# M_D_ext_power-solar-moved-usb.net
KiCad netlist of a schematic drawn in EAGLE
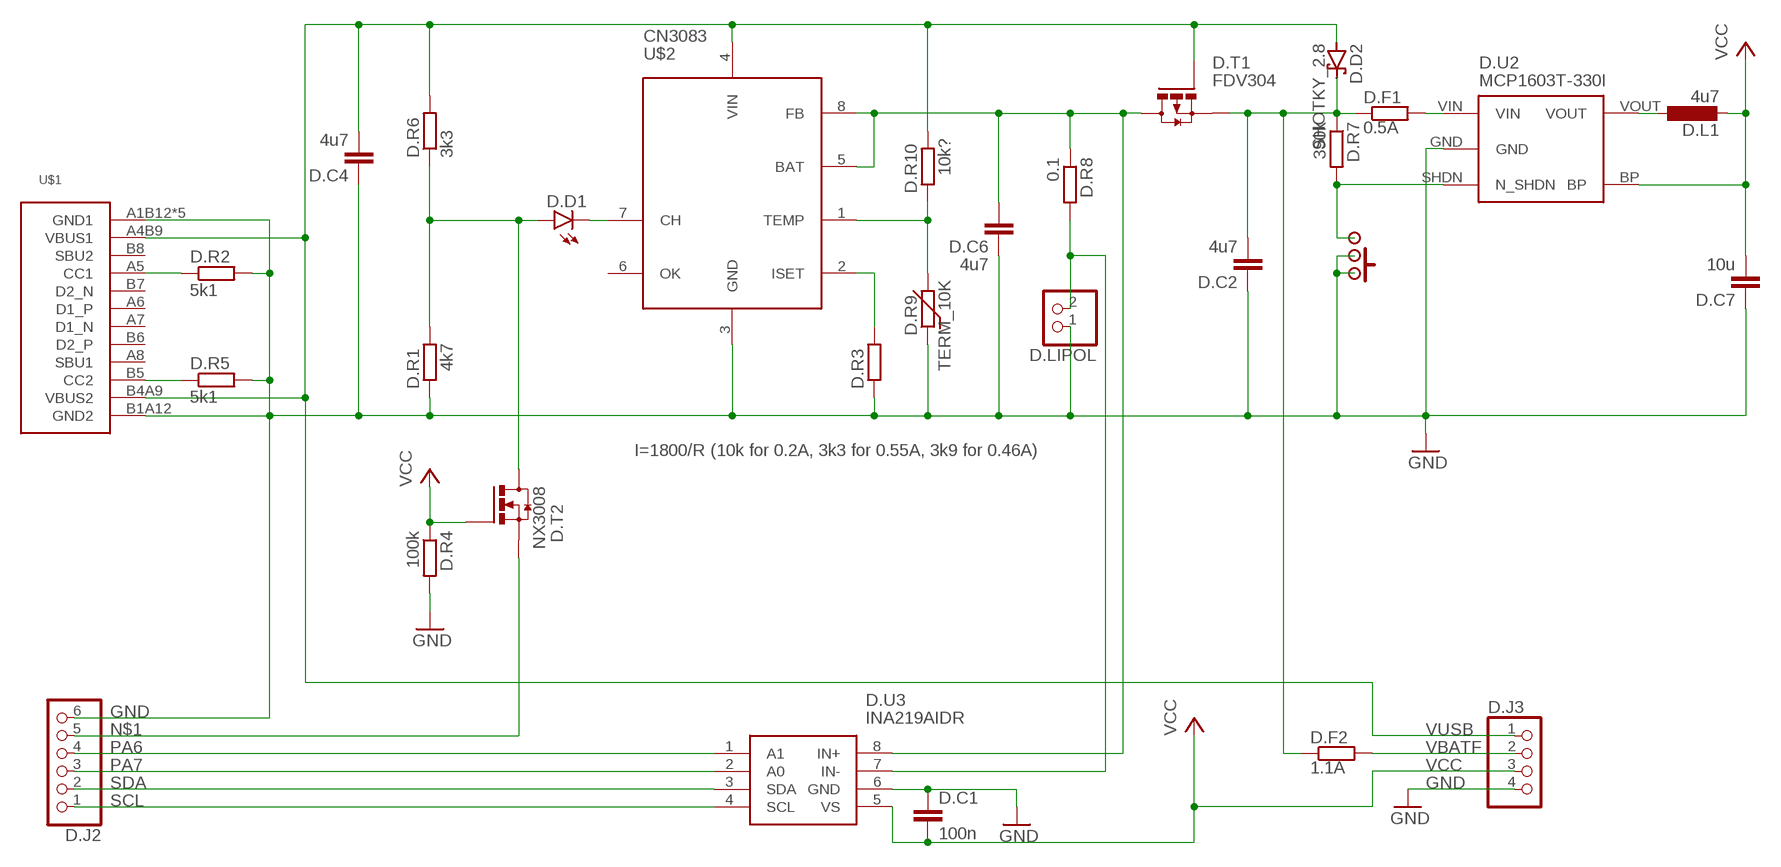
[diagram p0: schematic, sheet 1]

(export (version "E")
  (design (tool "Eeschema 10.0.6"))
  (components
    (comp (ref "D.C1")
      (value "100n")
      (footprint "eagle-import:C0603")
      (libsource (lib "eagle-import") (part "C-EUC0603"))
    )
    (comp (ref "D.C2")
      (value "4u7")
      (footprint "eagle-import:C0603")
      (libsource (lib "eagle-import") (part "C-EUC0603"))
    )
    (comp (ref "D.C4")
      (value "4u7")
      (footprint "eagle-import:C0603")
      (libsource (lib "eagle-import") (part "C-EUC0603"))
    )
    (comp (ref "D.C6")
      (value "4u7")
      (footprint "eagle-import:C0603")
      (libsource (lib "eagle-import") (part "C-EUC0603"))
    )
    (comp (ref "D.C7")
      (value "10u")
      (footprint "eagle-import:C0805")
      (libsource (lib "eagle-import") (part "C-EUC0805"))
    )
    (comp (ref "D.D1")
      (value "LEDCHIP-LED0603")
      (footprint "eagle-import:CHIP-LED0603")
      (libsource (lib "eagle-import") (part "LEDCHIP-LED0603"))
    )
    (comp (ref "D.D2")
      (value "SHOTKY_2.8")
      (footprint "eagle-import:SHOTKY_2.8")
      (libsource (lib "eagle-import") (part "SHOTKY_2.8"))
    )
    (comp (ref "D.F1")
      (value "0.5A")
      (footprint "eagle-import:R0805")
      (libsource (lib "eagle-import") (part "R-EU_R0805"))
    )
    (comp (ref "D.F2")
      (value "1.1A")
      (footprint "eagle-import:R0805")
      (libsource (lib "eagle-import") (part "R-EU_R0805"))
    )
    (comp (ref "D.J2")
      (value "PINHD-1X6")
      (footprint "eagle-import:1X06")
      (libsource (lib "eagle-import") (part "PINHD-1X6"))
    )
    (comp (ref "D.J3")
      (value "PINHD-1X4")
      (footprint "eagle-import:1X04")
      (libsource (lib "eagle-import") (part "PINHD-1X4"))
    )
    (comp (ref "D.L1")
      (value "4u7")
      (footprint "eagle-import:L3230M")
      (libsource (lib "eagle-import") (part "L-EUL3230M"))
    )
    (comp (ref "D.LIPOL")
      (value "PINHD-1X2")
      (footprint "eagle-import:1X02")
      (libsource (lib "eagle-import") (part "PINHD-1X2"))
    )
    (comp (ref "D.ON/OFF/RESET")
      (value "SWITCH")
      (footprint "eagle-import:SWITCH")
      (libsource (lib "eagle-import") (part "SWITCH"))
    )
    (comp (ref "D.R1")
      (value "4k7")
      (footprint "eagle-import:R0603")
      (libsource (lib "eagle-import") (part "R-EU_R0603"))
    )
    (comp (ref "D.R2")
      (value "5k1")
      (footprint "eagle-import:R0603")
      (libsource (lib "eagle-import") (part "R-EU_R0603"))
    )
    (comp (ref "D.R3")
      (value "I=1800/R (10k for 0.2A, 3k3 for 0.55A, 3k9 for 0.46A)")
      (footprint "eagle-import:R0603")
      (libsource (lib "eagle-import") (part "R-EU_R0603"))
    )
    (comp (ref "D.R4")
      (value "100k")
      (footprint "eagle-import:R0603")
      (libsource (lib "eagle-import") (part "R-EU_R0603"))
    )
    (comp (ref "D.R5")
      (value "5k1")
      (footprint "eagle-import:R0603")
      (libsource (lib "eagle-import") (part "R-EU_R0603"))
    )
    (comp (ref "D.R6")
      (value "3k3")
      (footprint "eagle-import:R0603")
      (libsource (lib "eagle-import") (part "R-EU_R0603"))
    )
    (comp (ref "D.R7")
      (value "390k")
      (footprint "eagle-import:R0603")
      (libsource (lib "eagle-import") (part "R-EU_R0603"))
    )
    (comp (ref "D.R8")
      (value "0.1")
      (footprint "eagle-import:R0805")
      (libsource (lib "eagle-import") (part "R-EU_R0805"))
    )
    (comp (ref "D.R9")
      (value "TERM_10K")
      (footprint "eagle-import:THERM")
      (libsource (lib "eagle-import") (part "THERM"))
    )
    (comp (ref "D.R10")
      (value "10k?")
      (footprint "eagle-import:R0603")
      (libsource (lib "eagle-import") (part "R-EU_R0603"))
    )
    (comp (ref "D.T1")
      (value "FDV304")
      (footprint "eagle-import:SO23")
      (libsource (lib "eagle-import") (part "P-MOSFET"))
    )
    (comp (ref "D.T2")
      (value "NX3008")
      (footprint "eagle-import:SO23")
      (libsource (lib "eagle-import") (part "N-MOSFET"))
    )
    (comp (ref "D.U2")
      (value "MCP1603T-330I")
      (footprint "eagle-import:SOT32-5")
      (libsource (lib "eagle-import") (part "STABILISER_APE8865"))
    )
    (comp (ref "D.U3")
      (value "INA219AIDR")
      (footprint "eagle-import:SOIC127P600X175-8N")
      (fields (field (name "MOUSER_PART_NUMBER") "595-INA219AIDR"))
      (libsource (lib "eagle-import") (part "INA219AIDR"))
    )
    (comp (ref "U$1")
      (value "USB-C")
      (footprint "eagle-import:USB-C")
      (libsource (lib "eagle-import") (part "USB-C"))
    )
    (comp (ref "U$2")
      (value "CN3083")
      (footprint "eagle-import:SOP8")
      (libsource (lib "eagle-import") (part "CN3083"))
    )
  )
  (nets
    (net (code "1") (name "/N$1") (class "Default")
      (node (ref "D.J2") (pin "5") (pinfunction "5_5") (pintype "passive"))
      (node (ref "D.T2") (pin "S") (pinfunction "S_S") (pintype "passive"))
    )
    (net (code "2") (name "/PA6") (class "Default")
      (node (ref "D.J2") (pin "4") (pinfunction "4_4") (pintype "passive"))
      (node (ref "D.U3") (pin "1") (pinfunction "A1_1") (pintype "bidirectional"))
    )
    (net (code "3") (name "/PA7") (class "Default")
      (node (ref "D.J2") (pin "3") (pinfunction "3_3") (pintype "passive"))
      (node (ref "D.U3") (pin "2") (pinfunction "A0_2") (pintype "bidirectional"))
    )
    (net (code "4") (name "/SCL") (class "Default")
      (node (ref "D.J2") (pin "1") (pinfunction "1_1") (pintype "passive"))
      (node (ref "D.U3") (pin "4") (pinfunction "SCL_4") (pintype "bidirectional"))
    )
    (net (code "5") (name "/SDA") (class "Default")
      (node (ref "D.J2") (pin "2") (pinfunction "2_2") (pintype "passive"))
      (node (ref "D.U3") (pin "3") (pinfunction "SDA_3") (pintype "bidirectional"))
    )
    (net (code "6") (name "/VBATF") (class "Default")
      (node (ref "D.F2") (pin "2") (pinfunction "2_2") (pintype "passive"))
      (node (ref "D.J3") (pin "2") (pinfunction "2_2") (pintype "passive"))
    )
    (net (code "7") (name "/VUSB") (class "Default")
      (node (ref "D.C4") (pin "2") (pinfunction "2_2") (pintype "passive"))
      (node (ref "D.D2") (pin "A") (pinfunction "A_A") (pintype "passive"))
      (node (ref "D.J3") (pin "1") (pinfunction "1_1") (pintype "passive"))
      (node (ref "D.R10") (pin "2") (pinfunction "2_2") (pintype "passive"))
      (node (ref "D.R6") (pin "2") (pinfunction "2_2") (pintype "passive"))
      (node (ref "D.T1") (pin "G") (pinfunction "G_G") (pintype "passive"))
      (node (ref "U$1") (pin "A4B9") (pinfunction "VBUS1_A4B9") (pintype "bidirectional"))
      (node (ref "U$1") (pin "B4A9") (pinfunction "VBUS2_B4A9") (pintype "bidirectional"))
      (node (ref "U$2") (pin "4") (pinfunction "VIN_4") (pintype "bidirectional"))
    )
    (net (code "8") (name "GND") (class "Default")
      (node (ref "D.C1") (pin "1") (pinfunction "1_1") (pintype "passive"))
      (node (ref "D.C2") (pin "1") (pinfunction "1_1") (pintype "passive"))
      (node (ref "D.C4") (pin "1") (pinfunction "1_1") (pintype "passive"))
      (node (ref "D.C6") (pin "1") (pinfunction "1_1") (pintype "passive"))
      (node (ref "D.C7") (pin "1") (pinfunction "1_1") (pintype "passive"))
      (node (ref "D.J2") (pin "6") (pinfunction "6_6") (pintype "passive"))
      (node (ref "D.J3") (pin "4") (pinfunction "4_4") (pintype "passive"))
      (node (ref "D.LIPOL") (pin "1") (pinfunction "1_1") (pintype "passive"))
      (node (ref "D.ON/OFF/RESET") (pin "P$1") (pinfunction "P$1_P$1") (pintype "bidirectional"))
      (node (ref "D.ON/OFF/RESET") (pin "P$2") (pinfunction "P$2_P$2") (pintype "bidirectional"))
      (node (ref "D.ON/OFF/RESET") (pin "P$4") (pinfunction "P$1_P$4") (pintype "bidirectional"))
      (node (ref "D.R1") (pin "1") (pinfunction "1_1") (pintype "passive"))
      (node (ref "D.R2") (pin "2") (pinfunction "2_2") (pintype "passive"))
      (node (ref "D.R3") (pin "1") (pinfunction "1_1") (pintype "passive"))
      (node (ref "D.R4") (pin "2") (pinfunction "2_2") (pintype "passive"))
      (node (ref "D.R5") (pin "2") (pinfunction "2_2") (pintype "passive"))
      (node (ref "D.R9") (pin "1") (pinfunction "1_1") (pintype "passive"))
      (node (ref "D.U2") (pin "GND") (pinfunction "GND_GND") (pintype "bidirectional"))
      (node (ref "D.U3") (pin "6") (pinfunction "GND_6") (pintype "bidirectional"))
      (node (ref "U$1") (pin "A1B12") (pinfunction "GND1_A1B12") (pintype "bidirectional"))
      (node (ref "U$1") (pin "B1A12") (pinfunction "GND2_B1A12") (pintype "bidirectional"))
      (node (ref "U$1") (pin "SH1") (pinfunction "GND1_SH1") (pintype "bidirectional"))
      (node (ref "U$1") (pin "SH2") (pinfunction "GND1_SH2") (pintype "bidirectional"))
      (node (ref "U$1") (pin "SH3") (pinfunction "GND1_SH3") (pintype "bidirectional"))
      (node (ref "U$1") (pin "SH4") (pinfunction "GND1_SH4") (pintype "bidirectional"))
      (node (ref "U$2") (pin "3") (pinfunction "GND_3") (pintype "bidirectional"))
    )
    (net (code "9") (name "Net-(D.D1-A)") (class "Default")
      (node (ref "D.D1") (pin "A1") (pinfunction "A_A1") (pintype "passive"))
      (node (ref "D.R1") (pin "2") (pinfunction "2_2") (pintype "passive"))
      (node (ref "D.R6") (pin "1") (pinfunction "1_1") (pintype "passive"))
      (node (ref "D.T2") (pin "D") (pinfunction "D_D") (pintype "passive"))
    )
    (net (code "10") (name "Net-(D.D1-C)") (class "Default")
      (node (ref "D.D1") (pin "C1") (pinfunction "C_C1") (pintype "passive"))
      (node (ref "U$2") (pin "7") (pinfunction "CH_7") (pintype "bidirectional"))
    )
    (net (code "11") (name "Net-(D.D2-C)") (class "Default")
      (node (ref "D.C2") (pin "2") (pinfunction "2_2") (pintype "passive"))
      (node (ref "D.D2") (pin "K") (pinfunction "C_K") (pintype "passive"))
      (node (ref "D.F1") (pin "1") (pinfunction "1_1") (pintype "passive"))
      (node (ref "D.F2") (pin "1") (pinfunction "1_1") (pintype "passive"))
      (node (ref "D.R7") (pin "1") (pinfunction "1_1") (pintype "passive"))
      (node (ref "D.T1") (pin "S") (pinfunction "S_S") (pintype "passive"))
    )
    (net (code "12") (name "Net-(D.F1-Pad2)") (class "Default")
      (node (ref "D.F1") (pin "2") (pinfunction "2_2") (pintype "passive"))
      (node (ref "D.U2") (pin "VIN") (pinfunction "VIN_VIN") (pintype "bidirectional"))
    )
    (net (code "13") (name "Net-(D.L1-Pad1)") (class "Default")
      (node (ref "D.L1") (pin "1") (pinfunction "1_1") (pintype "passive"))
      (node (ref "D.U2") (pin "VOUT") (pinfunction "VOUT_VOUT") (pintype "bidirectional"))
    )
    (net (code "14") (name "Net-(D.U2-N_SHDN)") (class "Default")
      (node (ref "D.ON/OFF/RESET") (pin "P$3") (pinfunction "P$3_P$3") (pintype "bidirectional"))
      (node (ref "D.ON/OFF/RESET") (pin "P$5") (pinfunction "P$3_P$5") (pintype "bidirectional"))
      (node (ref "D.R7") (pin "2") (pinfunction "2_2") (pintype "passive"))
      (node (ref "D.U2") (pin "SHDN") (pinfunction "N_SHDN_SHDN") (pintype "bidirectional"))
    )
    (net (code "15") (name "Net-(D.U3-IN+)") (class "Default")
      (node (ref "D.C6") (pin "2") (pinfunction "2_2") (pintype "passive"))
      (node (ref "D.R8") (pin "1") (pinfunction "1_1") (pintype "passive"))
      (node (ref "D.T1") (pin "D") (pinfunction "D_D") (pintype "passive"))
      (node (ref "D.U3") (pin "8") (pinfunction "IN+_8") (pintype "bidirectional"))
      (node (ref "U$2") (pin "5") (pinfunction "BAT_5") (pintype "bidirectional"))
      (node (ref "U$2") (pin "8") (pinfunction "FB_8") (pintype "bidirectional"))
    )
    (net (code "16") (name "Net-(D.U3-IN-)") (class "Default")
      (node (ref "D.LIPOL") (pin "2") (pinfunction "2_2") (pintype "passive"))
      (node (ref "D.R8") (pin "2") (pinfunction "2_2") (pintype "passive"))
      (node (ref "D.U3") (pin "7") (pinfunction "IN-_7") (pintype "bidirectional"))
    )
    (net (code "17") (name "Net-(U$1-CC1)") (class "Default")
      (node (ref "D.R2") (pin "1") (pinfunction "1_1") (pintype "passive"))
      (node (ref "U$1") (pin "A5") (pinfunction "CC1_A5") (pintype "bidirectional"))
    )
    (net (code "18") (name "Net-(U$1-CC2)") (class "Default")
      (node (ref "D.R5") (pin "1") (pinfunction "1_1") (pintype "passive"))
      (node (ref "U$1") (pin "B5") (pinfunction "CC2_B5") (pintype "bidirectional"))
    )
    (net (code "19") (name "Net-(U$2-ISET)") (class "Default")
      (node (ref "D.R3") (pin "2") (pinfunction "2_2") (pintype "passive"))
      (node (ref "U$2") (pin "2") (pinfunction "ISET_2") (pintype "bidirectional"))
    )
    (net (code "20") (name "Net-(U$2-TEMP)") (class "Default")
      (node (ref "D.R10") (pin "1") (pinfunction "1_1") (pintype "passive"))
      (node (ref "D.R9") (pin "2") (pinfunction "2_2") (pintype "passive"))
      (node (ref "U$2") (pin "1") (pinfunction "TEMP_1") (pintype "bidirectional"))
    )
    (net (code "21") (name "VCC") (class "Default")
      (node (ref "D.C1") (pin "2") (pinfunction "2_2") (pintype "passive"))
      (node (ref "D.C7") (pin "2") (pinfunction "2_2") (pintype "passive"))
      (node (ref "D.J3") (pin "3") (pinfunction "3_3") (pintype "passive"))
      (node (ref "D.L1") (pin "2") (pinfunction "2_2") (pintype "passive"))
      (node (ref "D.R4") (pin "1") (pinfunction "1_1") (pintype "passive"))
      (node (ref "D.T2") (pin "G") (pinfunction "G_G") (pintype "passive"))
      (node (ref "D.U2") (pin "BP") (pinfunction "BP_BP") (pintype "bidirectional"))
      (node (ref "D.U3") (pin "5") (pinfunction "VS_5") (pintype "bidirectional"))
    )
    (net (code "22") (name "unconnected-(U$1-D1_N-PadA7)") (class "Default")
      (node (ref "U$1") (pin "A7") (pinfunction "D1_N_A7") (pintype "bidirectional"))
    )
    (net (code "23") (name "unconnected-(U$1-D1_P-PadA6)") (class "Default")
      (node (ref "U$1") (pin "A6") (pinfunction "D1_P_A6") (pintype "bidirectional"))
    )
    (net (code "24") (name "unconnected-(U$1-D2_N-PadB7)") (class "Default")
      (node (ref "U$1") (pin "B7") (pinfunction "D2_N_B7") (pintype "bidirectional"))
    )
    (net (code "25") (name "unconnected-(U$1-D2_P-PadB6)") (class "Default")
      (node (ref "U$1") (pin "B6") (pinfunction "D2_P_B6") (pintype "bidirectional"))
    )
    (net (code "26") (name "unconnected-(U$1-SBU1-PadA8)") (class "Default")
      (node (ref "U$1") (pin "A8") (pinfunction "SBU1_A8") (pintype "bidirectional"))
    )
    (net (code "27") (name "unconnected-(U$1-SBU2-PadB8)") (class "Default")
      (node (ref "U$1") (pin "B8") (pinfunction "SBU2_B8") (pintype "bidirectional"))
    )
    (net (code "28") (name "unconnected-(U$2-OK-Pad6)") (class "Default")
      (node (ref "U$2") (pin "6") (pinfunction "OK_6") (pintype "bidirectional"))
    )
  )
)
